# DRV8701.net
KiCad netlist of a schematic drawn in EasyEDA Pro
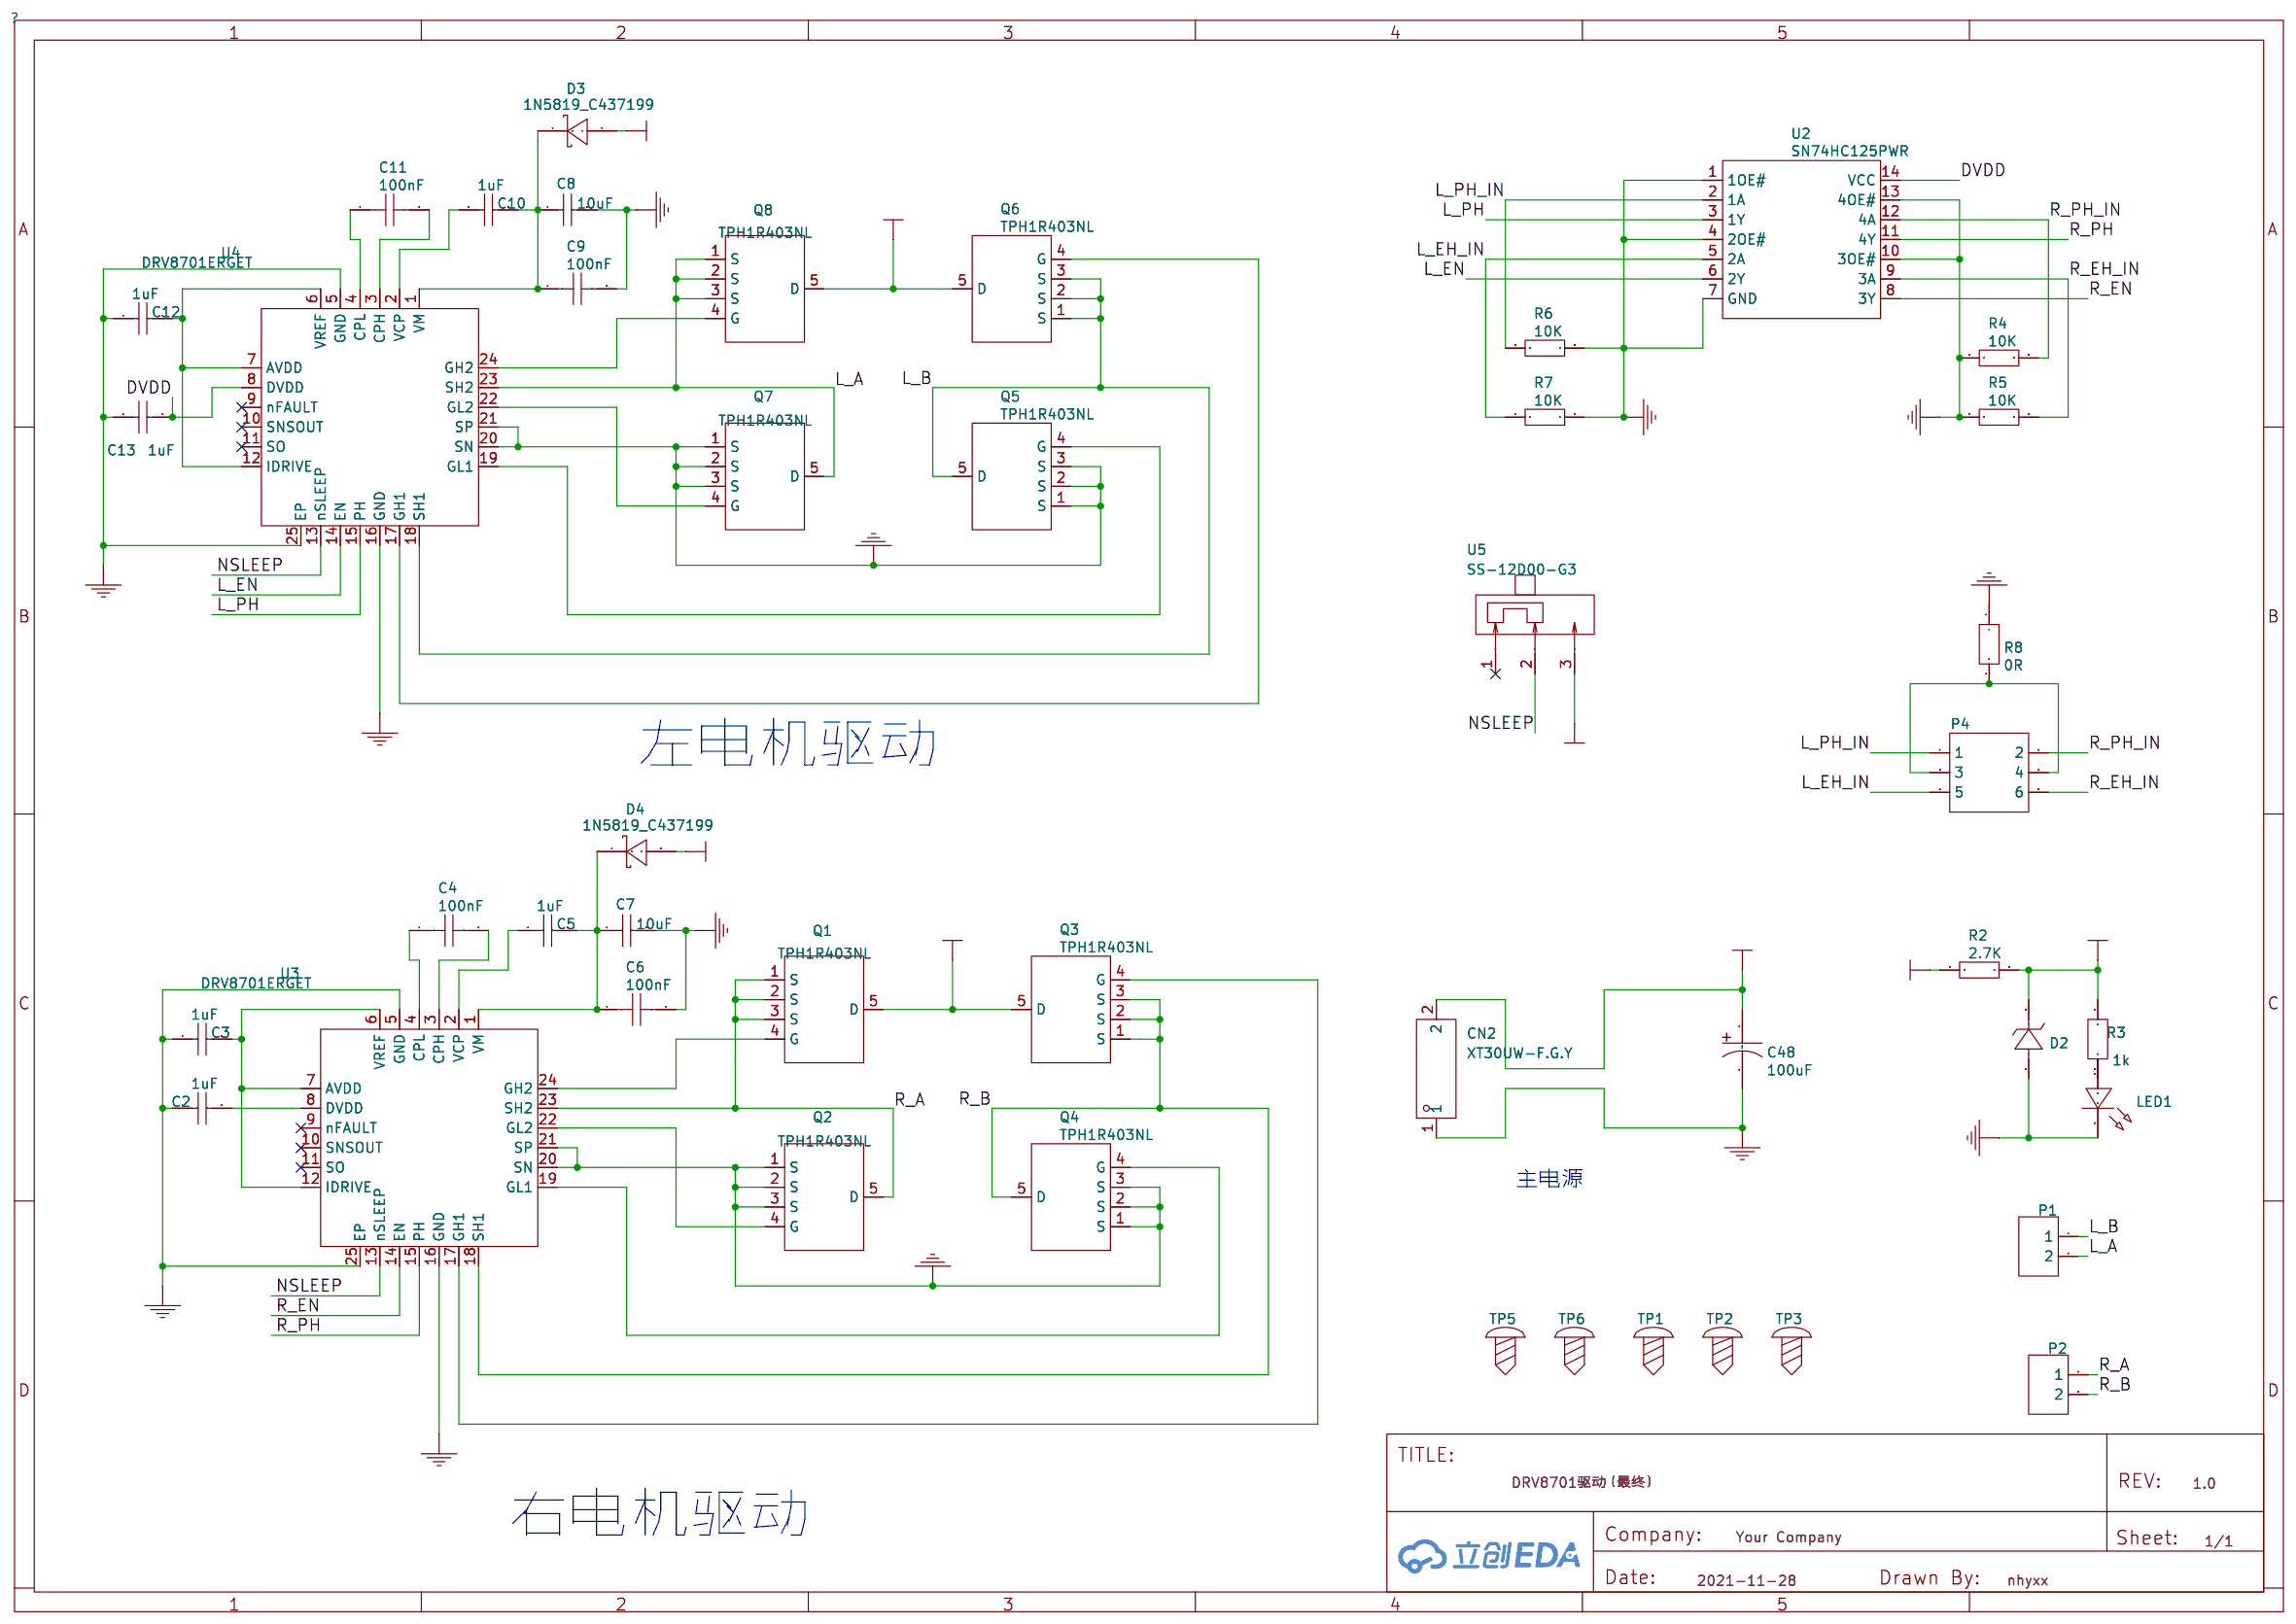
[diagram p0: schematic sheet]

(export (version "E")
  (design (tool "Eeschema 10.0.6"))
  (components
    (comp (ref "C2")
      (value "1uF")
      (footprint "easyedapro:C0603")
      (fields (field (name "Manufacturer Part") "CL21F105ZOFNNNE") (field (name "Manufacturer") "SAMSUNG"))
      (libsource (lib "easyedapro") (part "1uF"))
    )
    (comp (ref "C3")
      (value "1uF")
      (footprint "easyedapro:C0603")
      (fields (field (name "Manufacturer Part") "CL21F105ZOFNNNE") (field (name "Manufacturer") "SAMSUNG"))
      (libsource (lib "easyedapro") (part "1uF"))
    )
    (comp (ref "C4")
      (value "100nF")
      (footprint "easyedapro:C0603")
      (fields
        (field (name "Manufacturer Part") "CL21B104MBCNNNC")
        (field (name "Manufacturer") "Samsung Electro-Mechanics")
      )
      (libsource (lib "easyedapro") (part "100nF"))
    )
    (comp (ref "C5")
      (value "1uF")
      (footprint "easyedapro:C0603")
      (fields (field (name "Manufacturer Part") "CL21F105ZOFNNNE") (field (name "Manufacturer") "SAMSUNG"))
      (libsource (lib "easyedapro") (part "1uF"))
    )
    (comp (ref "C6")
      (value "100nF")
      (footprint "easyedapro:C0603")
      (fields
        (field (name "Manufacturer Part") "CL21B104MBCNNNC")
        (field (name "Manufacturer") "Samsung Electro-Mechanics")
      )
      (libsource (lib "easyedapro") (part "100nF"))
    )
    (comp (ref "C7")
      (value "10uF")
      (footprint "easyedapro:C0603")
      (fields (field (name "Manufacturer Part") "C2012X5R1E106KT000N") (field (name "Manufacturer") "TDK"))
      (libsource (lib "easyedapro") (part "10uF"))
    )
    (comp (ref "C8")
      (value "10uF")
      (footprint "easyedapro:C0603")
      (fields (field (name "Manufacturer Part") "C2012X5R1E106KT000N") (field (name "Manufacturer") "TDK"))
      (libsource (lib "easyedapro") (part "10uF"))
    )
    (comp (ref "C9")
      (value "100nF")
      (footprint "easyedapro:C0603")
      (fields
        (field (name "Manufacturer Part") "CL21B104MBCNNNC")
        (field (name "Manufacturer") "Samsung Electro-Mechanics")
      )
      (libsource (lib "easyedapro") (part "100nF"))
    )
    (comp (ref "C10")
      (value "1uF")
      (footprint "easyedapro:C0603")
      (fields (field (name "Manufacturer Part") "CL21F105ZOFNNNE") (field (name "Manufacturer") "SAMSUNG"))
      (libsource (lib "easyedapro") (part "1uF"))
    )
    (comp (ref "C11")
      (value "100nF")
      (footprint "easyedapro:C0603")
      (fields
        (field (name "Manufacturer Part") "CL21B104MBCNNNC")
        (field (name "Manufacturer") "Samsung Electro-Mechanics")
      )
      (libsource (lib "easyedapro") (part "100nF"))
    )
    (comp (ref "C12")
      (value "1uF")
      (footprint "easyedapro:C0603")
      (fields (field (name "Manufacturer Part") "CL21F105ZOFNNNE") (field (name "Manufacturer") "SAMSUNG"))
      (libsource (lib "easyedapro") (part "1uF"))
    )
    (comp (ref "C13")
      (value "1uF")
      (footprint "easyedapro:C0603")
      (fields (field (name "Manufacturer Part") "CL21F105ZOFNNNE") (field (name "Manufacturer") "SAMSUNG"))
      (libsource (lib "easyedapro") (part "1uF"))
    )
    (comp (ref "C48")
      (value "100uF")
      (footprint "easyedapro:CAP-TH_BD8.0-P3.50-D1.0-FD")
      (fields
        (field (name "Manufacturer Part") "SPZ1HM101F09O00RAXXX")
        (field (name "Manufacturer") "Aihua Group")
      )
      (libsource (lib "easyedapro") (part "100uF"))
    )
    (comp (ref "CN2")
      (value "XT30UW-F.G.Y")
      (footprint "easyedapro:CONN-TH_XT30UW-F.G.Y")
      (fields (field (name "Manufacturer") "AMASS(艾迈斯)"))
      (libsource (lib "easyedapro") (part "XT30UW-F.G.Y"))
    )
    (comp (ref "D2")
      (value "BZT52C3V3_C908185")
      (footprint "easyedapro:SOD-123_L2.7-W1.6-LS3.7-RD")
      (fields (field (name "Manufacturer Part") "BZT52C3V3") (field (name "Manufacturer") "FUXINSEMI"))
      (libsource (lib "easyedapro") (part "BZT52C3V3_C908185"))
    )
    (comp (ref "D3")
      (value "1N5819_C437199")
      (footprint "easyedapro:SMA_L4.4-W2.6-LS5.0-RD")
      (fields (field (name "Manufacturer Part") "1N5819") (field (name "Manufacturer") "KEXIN"))
      (libsource (lib "easyedapro") (part "1N5819_C437199"))
    )
    (comp (ref "D4")
      (value "1N5819_C437199")
      (footprint "easyedapro:SMA_L4.4-W2.6-LS5.0-RD")
      (fields (field (name "Manufacturer Part") "1N5819") (field (name "Manufacturer") "KEXIN"))
      (libsource (lib "easyedapro") (part "1N5819_C437199"))
    )
    (comp (ref "LED1")
      (value "LED-0805_R")
      (footprint "easyedapro:LED0603_BLUE")
      (fields
        (field (name "Manufacturer Part") "17-21SURC/S530-A3/TR8")
        (field (name "Manufacturer") "EVERLIGHT(台湾亿光)")
      )
      (libsource (lib "easyedapro") (part "LED-0805_R"))
    )
    (comp (ref "P1")
      (value "CONN-TH_2P-P5.00")
      (footprint "easyedapro:CONN-TH_2P-P5.00")
      (libsource (lib "easyedapro") (part "CONN-TH_2P-P5.00"))
    )
    (comp (ref "P2")
      (value "CONN-TH_2P-P5.00")
      (footprint "easyedapro:CONN-TH_2P-P5.00")
      (libsource (lib "easyedapro") (part "CONN-TH_2P-P5.00"))
    )
    (comp (ref "P4")
      (value "~")
      (footprint "easyedapro:HDR-TH_6P-P2.54-V-F-R2-C3-S2.54")
      (libsource (lib "easyedapro") (part "HDR-F-2.54_2x3"))
    )
    (comp (ref "Q1")
      (value "TPH1R403NL")
      (footprint "easyedapro:POWERVDFN-8_L6.2-W5.2-P1.27-LS6.0-BL")
      (fields (field (name "Manufacturer") "TOSHIBA"))
      (libsource (lib "") (part "TPH1R403NL_1"))
    )
    (comp (ref "Q2")
      (value "TPH1R403NL")
      (footprint "easyedapro:POWERVDFN-8_L6.2-W5.2-P1.27-LS6.0-BL")
      (fields (field (name "Manufacturer") "TOSHIBA"))
      (libsource (lib "") (part "TPH1R403NL_1"))
    )
    (comp (ref "Q3")
      (value "TPH1R403NL")
      (footprint "easyedapro:POWERVDFN-8_L6.2-W5.2-P1.27-LS6.0-BL")
      (fields (field (name "Manufacturer") "TOSHIBA"))
      (libsource (lib "easyedapro") (part "TPH1R403NL"))
    )
    (comp (ref "Q4")
      (value "TPH1R403NL")
      (footprint "easyedapro:POWERVDFN-8_L6.2-W5.2-P1.27-LS6.0-BL")
      (fields (field (name "Manufacturer") "TOSHIBA"))
      (libsource (lib "easyedapro") (part "TPH1R403NL"))
    )
    (comp (ref "Q5")
      (value "TPH1R403NL")
      (footprint "easyedapro:POWERVDFN-8_L6.2-W5.2-P1.27-LS6.0-BL")
      (fields (field (name "Manufacturer") "TOSHIBA"))
      (libsource (lib "easyedapro") (part "TPH1R403NL"))
    )
    (comp (ref "Q6")
      (value "TPH1R403NL")
      (footprint "easyedapro:POWERVDFN-8_L6.2-W5.2-P1.27-LS6.0-BL")
      (fields (field (name "Manufacturer") "TOSHIBA"))
      (libsource (lib "easyedapro") (part "TPH1R403NL"))
    )
    (comp (ref "Q7")
      (value "TPH1R403NL")
      (footprint "easyedapro:POWERVDFN-8_L6.2-W5.2-P1.27-LS6.0-BL")
      (fields (field (name "Manufacturer") "TOSHIBA"))
      (libsource (lib "") (part "TPH1R403NL_1"))
    )
    (comp (ref "Q8")
      (value "TPH1R403NL")
      (footprint "easyedapro:POWERVDFN-8_L6.2-W5.2-P1.27-LS6.0-BL")
      (fields (field (name "Manufacturer") "TOSHIBA"))
      (libsource (lib "") (part "TPH1R403NL_1"))
    )
    (comp (ref "R2")
      (value "2.7K")
      (footprint "easyedapro:R0603")
      (fields (field (name "Manufacturer Part") "0805W8F2701T5E") (field (name "Manufacturer") "UniOhm"))
      (libsource (lib "easyedapro") (part "2.7K"))
    )
    (comp (ref "R3") (value "1k") (footprint "easyedapro:R0603") (libsource (lib "easyedapro") (part "1k")))
    (comp (ref "R4")
      (value "10K")
      (footprint "easyedapro:R0603")
      (fields (field (name "Manufacturer Part") "RG2012P-103-B-T5") (field (name "Manufacturer") "SUSUMU"))
      (libsource (lib "easyedapro") (part "10K"))
    )
    (comp (ref "R5")
      (value "10K")
      (footprint "easyedapro:R0603")
      (fields (field (name "Manufacturer Part") "RG2012P-103-B-T5") (field (name "Manufacturer") "SUSUMU"))
      (libsource (lib "easyedapro") (part "10K"))
    )
    (comp (ref "R6")
      (value "10K")
      (footprint "easyedapro:R0603")
      (fields (field (name "Manufacturer Part") "RG2012P-103-B-T5") (field (name "Manufacturer") "SUSUMU"))
      (libsource (lib "easyedapro") (part "10K"))
    )
    (comp (ref "R7")
      (value "10K")
      (footprint "easyedapro:R0603")
      (fields (field (name "Manufacturer Part") "RG2012P-103-B-T5") (field (name "Manufacturer") "SUSUMU"))
      (libsource (lib "easyedapro") (part "10K"))
    )
    (comp (ref "R8") (value "0R") (footprint "easyedapro:R1206") (libsource (lib "easyedapro") (part "0R")))
    (comp (ref "TP1")
      (value "M3铜柱")
      (footprint "easyedapro:M3铜柱")
      (libsource (lib "easyedapro") (part "M3铜柱"))
    )
    (comp (ref "TP2")
      (value "M3铜柱")
      (footprint "easyedapro:M3铜柱")
      (libsource (lib "easyedapro") (part "M3铜柱"))
    )
    (comp (ref "TP3")
      (value "M3铜柱")
      (footprint "easyedapro:M3铜柱")
      (libsource (lib "easyedapro") (part "M3铜柱"))
    )
    (comp (ref "TP5")
      (value "M3铜柱")
      (footprint "easyedapro:M3铜柱")
      (libsource (lib "easyedapro") (part "M3铜柱"))
    )
    (comp (ref "TP6")
      (value "M3铜柱")
      (footprint "easyedapro:M3铜柱")
      (libsource (lib "easyedapro") (part "M3铜柱"))
    )
    (comp (ref "U2")
      (value "SN74HC125PWR")
      (footprint "easyedapro:TSSOP-14_L5.0-W4.4-P0.65-LS6.5-BL")
      (fields (field (name "Manufacturer") "Texas Instruments"))
      (libsource (lib "easyedapro") (part "SN74HC125PWR"))
    )
    (comp (ref "U3")
      (value "DRV8701ERGET")
      (footprint "easyedapro:VQFN-24_L4.0-W4.0-P0.50-LS4.0-BL-EP")
      (fields (field (name "Manufacturer") "TI"))
      (libsource (lib "easyedapro") (part "DRV8701ERGET"))
    )
    (comp (ref "U4")
      (value "DRV8701ERGET")
      (footprint "easyedapro:VQFN-24_L4.0-W4.0-P0.50-LS4.0-BL-EP")
      (fields (field (name "Manufacturer") "TI"))
      (libsource (lib "easyedapro") (part "DRV8701ERGET"))
    )
    (comp (ref "U5")
      (value "SS-12D00-G3")
      (footprint "easyedapro:SW-TH_3P-L8.8-W3.9-P2.50_SS12D00G3")
      (description "操作正拨 插件立式 尺寸大型 两档位")
      (fields (field (name "Manufacturer") "SOFNG(硕方)"))
      (libsource (lib "easyedapro") (part "SS-12D00-G3"))
    )
  )
  (nets
    (net (code "1") (name "/DVDD") (class "Default")
      (node (ref "C13") (pin "2") (pinfunction "2_2") (pintype "input"))
      (node (ref "U2") (pin "14") (pinfunction "VCC_14") (pintype "unspecified"))
      (node (ref "U4") (pin "8") (pinfunction "DVDD_8") (pintype "unspecified"))
    )
    (net (code "2") (name "/L_A") (class "Default")
      (node (ref "P1") (pin "2") (pinfunction "2_2") (pintype "unspecified"))
      (node (ref "Q7") (pin "5") (pinfunction "D_5") (pintype "unspecified"))
      (node (ref "Q8") (pin "1") (pinfunction "S_1") (pintype "unspecified"))
      (node (ref "Q8") (pin "2") (pinfunction "S_2") (pintype "unspecified"))
      (node (ref "Q8") (pin "3") (pinfunction "S_3") (pintype "unspecified"))
      (node (ref "U4") (pin "23") (pinfunction "SH2_23") (pintype "unspecified"))
    )
    (net (code "3") (name "/L_B") (class "Default")
      (node (ref "P1") (pin "1") (pinfunction "1_1") (pintype "unspecified"))
      (node (ref "Q5") (pin "5") (pinfunction "D_5") (pintype "unspecified"))
      (node (ref "Q6") (pin "1") (pinfunction "S_1") (pintype "unspecified"))
      (node (ref "Q6") (pin "2") (pinfunction "S_2") (pintype "unspecified"))
      (node (ref "Q6") (pin "3") (pinfunction "S_3") (pintype "unspecified"))
      (node (ref "U4") (pin "18") (pinfunction "SH1_18") (pintype "unspecified"))
    )
    (net (code "4") (name "/L_EH_IN") (class "Default")
      (node (ref "P4") (pin "5") (pinfunction "5_5") (pintype "input"))
      (node (ref "R7") (pin "1") (pinfunction "1_1") (pintype "input"))
      (node (ref "U2") (pin "5") (pinfunction "2A_5") (pintype "unspecified"))
    )
    (net (code "5") (name "/L_EN") (class "Default")
      (node (ref "U2") (pin "6") (pinfunction "2Y_6") (pintype "unspecified"))
      (node (ref "U4") (pin "14") (pinfunction "EN_14") (pintype "unspecified"))
    )
    (net (code "6") (name "/L_PH") (class "Default")
      (node (ref "U2") (pin "3") (pinfunction "1Y_3") (pintype "unspecified"))
      (node (ref "U4") (pin "15") (pinfunction "PH_15") (pintype "unspecified"))
    )
    (net (code "7") (name "/L_PH_IN") (class "Default")
      (node (ref "P4") (pin "1") (pinfunction "1_1") (pintype "input"))
      (node (ref "R6") (pin "1") (pinfunction "1_1") (pintype "input"))
      (node (ref "U2") (pin "2") (pinfunction "1A_2") (pintype "unspecified"))
    )
    (net (code "8") (name "/NSLEEP") (class "Default")
      (node (ref "U3") (pin "13") (pinfunction "nSLEEP_13") (pintype "unspecified"))
      (node (ref "U4") (pin "13") (pinfunction "nSLEEP_13") (pintype "unspecified"))
      (node (ref "U5") (pin "2") (pinfunction "2_2") (pintype "unspecified"))
    )
    (net (code "9") (name "/R_A") (class "Default")
      (node (ref "P2") (pin "1") (pinfunction "1_1") (pintype "unspecified"))
      (node (ref "Q1") (pin "1") (pinfunction "S_1") (pintype "unspecified"))
      (node (ref "Q1") (pin "2") (pinfunction "S_2") (pintype "unspecified"))
      (node (ref "Q1") (pin "3") (pinfunction "S_3") (pintype "unspecified"))
      (node (ref "Q2") (pin "5") (pinfunction "D_5") (pintype "unspecified"))
      (node (ref "U3") (pin "23") (pinfunction "SH2_23") (pintype "unspecified"))
    )
    (net (code "10") (name "/R_B") (class "Default")
      (node (ref "P2") (pin "2") (pinfunction "2_2") (pintype "unspecified"))
      (node (ref "Q3") (pin "1") (pinfunction "S_1") (pintype "unspecified"))
      (node (ref "Q3") (pin "2") (pinfunction "S_2") (pintype "unspecified"))
      (node (ref "Q3") (pin "3") (pinfunction "S_3") (pintype "unspecified"))
      (node (ref "Q4") (pin "5") (pinfunction "D_5") (pintype "unspecified"))
      (node (ref "U3") (pin "18") (pinfunction "SH1_18") (pintype "unspecified"))
    )
    (net (code "11") (name "/R_EH_IN") (class "Default")
      (node (ref "P4") (pin "6") (pinfunction "6_6") (pintype "input"))
      (node (ref "R5") (pin "2") (pinfunction "2_2") (pintype "input"))
      (node (ref "U2") (pin "9") (pinfunction "3A_9") (pintype "unspecified"))
    )
    (net (code "12") (name "/R_EN") (class "Default")
      (node (ref "U2") (pin "8") (pinfunction "3Y_8") (pintype "unspecified"))
      (node (ref "U3") (pin "14") (pinfunction "EN_14") (pintype "unspecified"))
    )
    (net (code "13") (name "/R_PH") (class "Default")
      (node (ref "U2") (pin "11") (pinfunction "4Y_11") (pintype "unspecified"))
      (node (ref "U3") (pin "15") (pinfunction "PH_15") (pintype "unspecified"))
    )
    (net (code "14") (name "/R_PH_IN") (class "Default")
      (node (ref "P4") (pin "2") (pinfunction "2_2") (pintype "input"))
      (node (ref "R4") (pin "2") (pinfunction "2_2") (pintype "input"))
      (node (ref "U2") (pin "12") (pinfunction "4A_12") (pintype "unspecified"))
    )
    (net (code "15") (name "3V3") (class "Default")
      (node (ref "D2") (pin "1") (pinfunction "K_1") (pintype "unspecified"))
      (node (ref "R2") (pin "2") (pinfunction "2_2") (pintype "input"))
      (node (ref "R3") (pin "1") (pinfunction "1_1") (pintype "unspecified"))
      (node (ref "U5") (pin "3") (pinfunction "3_3") (pintype "unspecified"))
    )
    (net (code "16") (name "GND") (class "Default")
      (node (ref "C12") (pin "1") (pinfunction "1_1") (pintype "input"))
      (node (ref "C13") (pin "1") (pinfunction "1_1") (pintype "input"))
      (node (ref "C2") (pin "1") (pinfunction "1_1") (pintype "input"))
      (node (ref "C3") (pin "1") (pinfunction "1_1") (pintype "input"))
      (node (ref "C48") (pin "2") (pinfunction "2_2") (pintype "unspecified"))
      (node (ref "C6") (pin "2") (pinfunction "2_2") (pintype "unspecified"))
      (node (ref "C7") (pin "2") (pinfunction "2_2") (pintype "input"))
      (node (ref "C8") (pin "2") (pinfunction "2_2") (pintype "input"))
      (node (ref "C9") (pin "2") (pinfunction "2_2") (pintype "unspecified"))
      (node (ref "CN2") (pin "1") (pinfunction "1_1") (pintype "unspecified"))
      (node (ref "D2") (pin "2") (pinfunction "A_2") (pintype "unspecified"))
      (node (ref "LED1") (pin "2") (pinfunction "2_2") (pintype "unspecified"))
      (node (ref "Q2") (pin "1") (pinfunction "S_1") (pintype "unspecified"))
      (node (ref "Q2") (pin "2") (pinfunction "S_2") (pintype "unspecified"))
      (node (ref "Q2") (pin "3") (pinfunction "S_3") (pintype "unspecified"))
      (node (ref "Q4") (pin "1") (pinfunction "S_1") (pintype "unspecified"))
      (node (ref "Q4") (pin "2") (pinfunction "S_2") (pintype "unspecified"))
      (node (ref "Q4") (pin "3") (pinfunction "S_3") (pintype "unspecified"))
      (node (ref "Q5") (pin "1") (pinfunction "S_1") (pintype "unspecified"))
      (node (ref "Q5") (pin "2") (pinfunction "S_2") (pintype "unspecified"))
      (node (ref "Q5") (pin "3") (pinfunction "S_3") (pintype "unspecified"))
      (node (ref "Q7") (pin "1") (pinfunction "S_1") (pintype "unspecified"))
      (node (ref "Q7") (pin "2") (pinfunction "S_2") (pintype "unspecified"))
      (node (ref "Q7") (pin "3") (pinfunction "S_3") (pintype "unspecified"))
      (node (ref "R4") (pin "1") (pinfunction "1_1") (pintype "input"))
      (node (ref "R5") (pin "1") (pinfunction "1_1") (pintype "input"))
      (node (ref "R6") (pin "2") (pinfunction "2_2") (pintype "input"))
      (node (ref "R7") (pin "2") (pinfunction "2_2") (pintype "input"))
      (node (ref "R8") (pin "1") (pinfunction "1_1") (pintype "unspecified"))
      (node (ref "U2") (pin "1") (pinfunction "1OE#_1") (pintype "unspecified"))
      (node (ref "U2") (pin "10") (pinfunction "3OE#_10") (pintype "unspecified"))
      (node (ref "U2") (pin "13") (pinfunction "4OE#_13") (pintype "unspecified"))
      (node (ref "U2") (pin "4") (pinfunction "2OE#_4") (pintype "unspecified"))
      (node (ref "U2") (pin "7") (pinfunction "GND_7") (pintype "unspecified"))
      (node (ref "U3") (pin "16") (pinfunction "GND_16") (pintype "unspecified"))
      (node (ref "U3") (pin "20") (pinfunction "SN_20") (pintype "unspecified"))
      (node (ref "U3") (pin "21") (pinfunction "SP_21") (pintype "unspecified"))
      (node (ref "U3") (pin "25") (pinfunction "EP_25") (pintype "unspecified"))
      (node (ref "U3") (pin "5") (pinfunction "GND_5") (pintype "unspecified"))
      (node (ref "U4") (pin "16") (pinfunction "GND_16") (pintype "unspecified"))
      (node (ref "U4") (pin "20") (pinfunction "SN_20") (pintype "unspecified"))
      (node (ref "U4") (pin "21") (pinfunction "SP_21") (pintype "unspecified"))
      (node (ref "U4") (pin "25") (pinfunction "EP_25") (pintype "unspecified"))
      (node (ref "U4") (pin "5") (pinfunction "GND_5") (pintype "unspecified"))
    )
    (net (code "17") (name "Net-(D3-C)") (class "Default")
      (node (ref "C10") (pin "2") (pinfunction "2_2") (pintype "input"))
      (node (ref "C8") (pin "1") (pinfunction "1_1") (pintype "input"))
      (node (ref "C9") (pin "1") (pinfunction "1_1") (pintype "unspecified"))
      (node (ref "D3") (pin "1") (pinfunction "C_1") (pintype "unspecified"))
      (node (ref "U4") (pin "1") (pinfunction "VM_1") (pintype "unspecified"))
    )
    (net (code "18") (name "Net-(D4-C)") (class "Default")
      (node (ref "C5") (pin "2") (pinfunction "2_2") (pintype "input"))
      (node (ref "C6") (pin "1") (pinfunction "1_1") (pintype "unspecified"))
      (node (ref "C7") (pin "1") (pinfunction "1_1") (pintype "input"))
      (node (ref "D4") (pin "1") (pinfunction "C_1") (pintype "unspecified"))
      (node (ref "U3") (pin "1") (pinfunction "VM_1") (pintype "unspecified"))
    )
    (net (code "19") (name "Net-(LED1-Pad1)") (class "Default")
      (node (ref "LED1") (pin "1") (pinfunction "1_1") (pintype "unspecified"))
      (node (ref "R3") (pin "2") (pinfunction "2_2") (pintype "unspecified"))
    )
    (net (code "20") (name "Net-(P4-Pad3)") (class "Default")
      (node (ref "P4") (pin "3") (pinfunction "3_3") (pintype "input"))
      (node (ref "P4") (pin "4") (pinfunction "4_4") (pintype "input"))
      (node (ref "R8") (pin "2") (pinfunction "2_2") (pintype "unspecified"))
    )
    (net (code "21") (name "Net-(Q1-G)") (class "Default")
      (node (ref "Q1") (pin "4") (pinfunction "G_4") (pintype "unspecified"))
      (node (ref "U3") (pin "24") (pinfunction "GH2_24") (pintype "unspecified"))
    )
    (net (code "22") (name "Net-(Q2-G)") (class "Default")
      (node (ref "Q2") (pin "4") (pinfunction "G_4") (pintype "unspecified"))
      (node (ref "U3") (pin "22") (pinfunction "GL2_22") (pintype "unspecified"))
    )
    (net (code "23") (name "Net-(Q3-G)") (class "Default")
      (node (ref "Q3") (pin "4") (pinfunction "G_4") (pintype "unspecified"))
      (node (ref "U3") (pin "17") (pinfunction "GH1_17") (pintype "unspecified"))
    )
    (net (code "24") (name "Net-(Q4-G)") (class "Default")
      (node (ref "Q4") (pin "4") (pinfunction "G_4") (pintype "unspecified"))
      (node (ref "U3") (pin "19") (pinfunction "GL1_19") (pintype "unspecified"))
    )
    (net (code "25") (name "Net-(Q5-G)") (class "Default")
      (node (ref "Q5") (pin "4") (pinfunction "G_4") (pintype "unspecified"))
      (node (ref "U4") (pin "19") (pinfunction "GL1_19") (pintype "unspecified"))
    )
    (net (code "26") (name "Net-(Q6-G)") (class "Default")
      (node (ref "Q6") (pin "4") (pinfunction "G_4") (pintype "unspecified"))
      (node (ref "U4") (pin "17") (pinfunction "GH1_17") (pintype "unspecified"))
    )
    (net (code "27") (name "Net-(Q7-G)") (class "Default")
      (node (ref "Q7") (pin "4") (pinfunction "G_4") (pintype "unspecified"))
      (node (ref "U4") (pin "22") (pinfunction "GL2_22") (pintype "unspecified"))
    )
    (net (code "28") (name "Net-(Q8-G)") (class "Default")
      (node (ref "Q8") (pin "4") (pinfunction "G_4") (pintype "unspecified"))
      (node (ref "U4") (pin "24") (pinfunction "GH2_24") (pintype "unspecified"))
    )
    (net (code "29") (name "Net-(U3-AVDD)") (class "Default")
      (node (ref "C3") (pin "2") (pinfunction "2_2") (pintype "input"))
      (node (ref "U3") (pin "12") (pinfunction "IDRIVE_12") (pintype "unspecified"))
      (node (ref "U3") (pin "6") (pinfunction "VREF_6") (pintype "unspecified"))
      (node (ref "U3") (pin "7") (pinfunction "AVDD_7") (pintype "unspecified"))
    )
    (net (code "30") (name "Net-(U3-CPH)") (class "Default")
      (node (ref "C4") (pin "2") (pinfunction "2_2") (pintype "unspecified"))
      (node (ref "U3") (pin "3") (pinfunction "CPH_3") (pintype "unspecified"))
    )
    (net (code "31") (name "Net-(U3-CPL)") (class "Default")
      (node (ref "C4") (pin "1") (pinfunction "1_1") (pintype "unspecified"))
      (node (ref "U3") (pin "4") (pinfunction "CPL_4") (pintype "unspecified"))
    )
    (net (code "32") (name "Net-(U3-DVDD)") (class "Default")
      (node (ref "C2") (pin "2") (pinfunction "2_2") (pintype "input"))
      (node (ref "U3") (pin "8") (pinfunction "DVDD_8") (pintype "unspecified"))
    )
    (net (code "33") (name "Net-(U3-VCP)") (class "Default")
      (node (ref "C5") (pin "1") (pinfunction "1_1") (pintype "input"))
      (node (ref "U3") (pin "2") (pinfunction "VCP_2") (pintype "unspecified"))
    )
    (net (code "34") (name "Net-(U4-AVDD)") (class "Default")
      (node (ref "C12") (pin "2") (pinfunction "2_2") (pintype "input"))
      (node (ref "U4") (pin "12") (pinfunction "IDRIVE_12") (pintype "unspecified"))
      (node (ref "U4") (pin "6") (pinfunction "VREF_6") (pintype "unspecified"))
      (node (ref "U4") (pin "7") (pinfunction "AVDD_7") (pintype "unspecified"))
    )
    (net (code "35") (name "Net-(U4-CPH)") (class "Default")
      (node (ref "C11") (pin "2") (pinfunction "2_2") (pintype "unspecified"))
      (node (ref "U4") (pin "3") (pinfunction "CPH_3") (pintype "unspecified"))
    )
    (net (code "36") (name "Net-(U4-CPL)") (class "Default")
      (node (ref "C11") (pin "1") (pinfunction "1_1") (pintype "unspecified"))
      (node (ref "U4") (pin "4") (pinfunction "CPL_4") (pintype "unspecified"))
    )
    (net (code "37") (name "Net-(U4-VCP)") (class "Default")
      (node (ref "C10") (pin "1") (pinfunction "1_1") (pintype "input"))
      (node (ref "U4") (pin "2") (pinfunction "VCP_2") (pintype "unspecified"))
    )
    (net (code "38") (name "VM") (class "Default")
      (node (ref "C48") (pin "1") (pinfunction "1_1") (pintype "unspecified"))
      (node (ref "CN2") (pin "2") (pinfunction "2_2") (pintype "unspecified"))
      (node (ref "D3") (pin "2") (pinfunction "A_2") (pintype "unspecified"))
      (node (ref "D4") (pin "2") (pinfunction "A_2") (pintype "unspecified"))
      (node (ref "Q1") (pin "5") (pinfunction "D_5") (pintype "unspecified"))
      (node (ref "Q3") (pin "5") (pinfunction "D_5") (pintype "unspecified"))
      (node (ref "Q6") (pin "5") (pinfunction "D_5") (pintype "unspecified"))
      (node (ref "Q8") (pin "5") (pinfunction "D_5") (pintype "unspecified"))
      (node (ref "R2") (pin "1") (pinfunction "1_1") (pintype "input"))
    )
    (net (code "39") (name "unconnected-(U3-SNSOUT-Pad10)") (class "Default")
      (node (ref "U3") (pin "10") (pinfunction "SNSOUT_10") (pintype "unspecified+no_connect"))
    )
    (net (code "40") (name "unconnected-(U3-SO-Pad11)") (class "Default")
      (node (ref "U3") (pin "11") (pinfunction "SO_11") (pintype "unspecified+no_connect"))
    )
    (net (code "41") (name "unconnected-(U3-nFAULT-Pad9)") (class "Default")
      (node (ref "U3") (pin "9") (pinfunction "nFAULT_9") (pintype "unspecified+no_connect"))
    )
    (net (code "42") (name "unconnected-(U4-SNSOUT-Pad10)") (class "Default")
      (node (ref "U4") (pin "10") (pinfunction "SNSOUT_10") (pintype "unspecified+no_connect"))
    )
    (net (code "43") (name "unconnected-(U4-SO-Pad11)") (class "Default")
      (node (ref "U4") (pin "11") (pinfunction "SO_11") (pintype "unspecified+no_connect"))
    )
    (net (code "44") (name "unconnected-(U4-nFAULT-Pad9)") (class "Default")
      (node (ref "U4") (pin "9") (pinfunction "nFAULT_9") (pintype "unspecified+no_connect"))
    )
    (net (code "45") (name "unconnected-(U5-Pad1)") (class "Default")
      (node (ref "U5") (pin "1") (pinfunction "1_1") (pintype "unspecified+no_connect"))
    )
  )
)
